# Sensor_Board_Layout.net
KiCad netlist of a schematic drawn in EAGLE
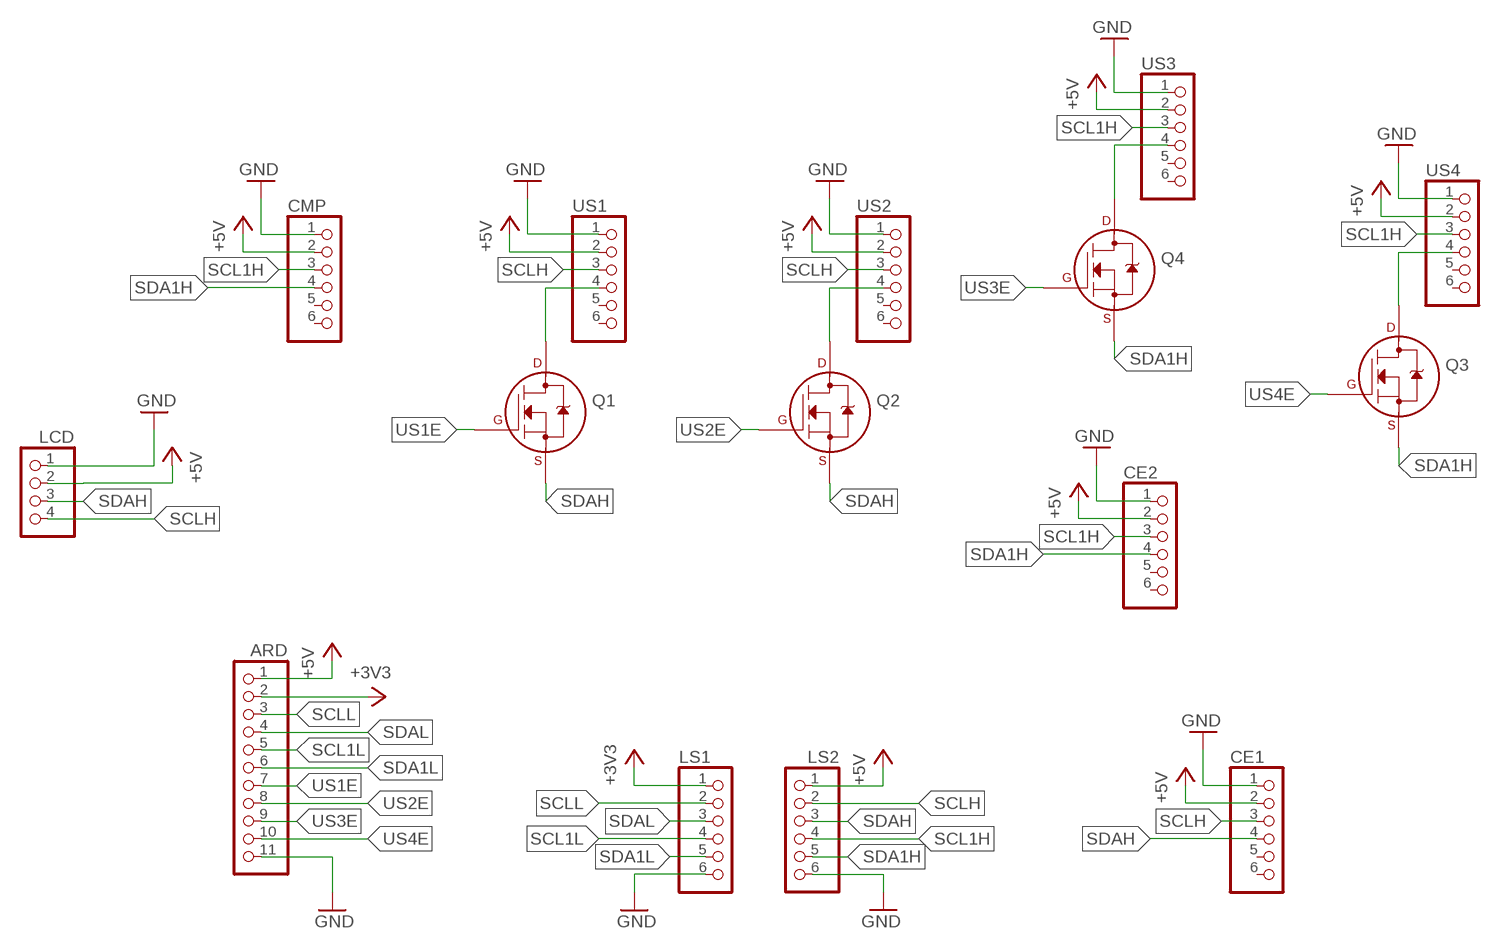
[diagram p0: schematic, sheet 1]

(export (version "E")
  (design (tool "Eeschema 10.0.6"))
  (components
    (comp (ref "ARD")
      (value "PINHD-1X11")
      (footprint "eagle-import:1X11")
      (libsource (lib "eagle-import") (part "PINHD-1X11"))
    )
    (comp (ref "CE1")
      (value "PINHD-1X6")
      (footprint "eagle-import:1X06")
      (libsource (lib "eagle-import") (part "PINHD-1X6"))
    )
    (comp (ref "CE2")
      (value "PINHD-1X6")
      (footprint "eagle-import:1X06")
      (libsource (lib "eagle-import") (part "PINHD-1X6"))
    )
    (comp (ref "CMP")
      (value "PINHD-1X6")
      (footprint "eagle-import:1X06")
      (libsource (lib "eagle-import") (part "PINHD-1X6"))
    )
    (comp (ref "LCD")
      (value "PINHD-1X4")
      (footprint "eagle-import:1X04")
      (libsource (lib "eagle-import") (part "PINHD-1X4"))
    )
    (comp (ref "LS1")
      (value "PINHD-1X6")
      (footprint "eagle-import:1X06")
      (libsource (lib "eagle-import") (part "PINHD-1X6"))
    )
    (comp (ref "LS2")
      (value "PINHD-1X6")
      (footprint "eagle-import:1X06")
      (libsource (lib "eagle-import") (part "PINHD-1X6"))
    )
    (comp (ref "Q1")
      (value "2N7000_TO92")
      (footprint "eagle-import:TO-92")
      (libsource (lib "eagle-import") (part "2N700_TO920"))
    )
    (comp (ref "Q2")
      (value "2N7000_TO92")
      (footprint "eagle-import:TO-92")
      (libsource (lib "eagle-import") (part "2N700_TO920"))
    )
    (comp (ref "Q3")
      (value "2N7000_TO92")
      (footprint "eagle-import:TO-92")
      (libsource (lib "eagle-import") (part "2N700_TO920"))
    )
    (comp (ref "Q4")
      (value "2N7000_TO92")
      (footprint "eagle-import:TO-92")
      (libsource (lib "eagle-import") (part "2N700_TO920"))
    )
    (comp (ref "US1")
      (value "PINHD-1X6")
      (footprint "eagle-import:1X06")
      (libsource (lib "eagle-import") (part "PINHD-1X6"))
    )
    (comp (ref "US2")
      (value "PINHD-1X6")
      (footprint "eagle-import:1X06")
      (libsource (lib "eagle-import") (part "PINHD-1X6"))
    )
    (comp (ref "US3")
      (value "PINHD-1X6")
      (footprint "eagle-import:1X06")
      (libsource (lib "eagle-import") (part "PINHD-1X6"))
    )
    (comp (ref "US4")
      (value "PINHD-1X6")
      (footprint "eagle-import:1X06")
      (libsource (lib "eagle-import") (part "PINHD-1X6"))
    )
  )
  (nets
    (net (code "1") (name "+3V3") (class "Default")
      (node (ref "ARD") (pin "2") (pinfunction "2_2") (pintype "passive"))
      (node (ref "LS1") (pin "1") (pinfunction "1_1") (pintype "passive"))
    )
    (net (code "2") (name "+5V") (class "Default")
      (node (ref "ARD") (pin "1") (pinfunction "1_1") (pintype "passive"))
      (node (ref "CE1") (pin "2") (pinfunction "2_2") (pintype "passive"))
      (node (ref "CE2") (pin "2") (pinfunction "2_2") (pintype "passive"))
      (node (ref "CMP") (pin "2") (pinfunction "2_2") (pintype "passive"))
      (node (ref "LCD") (pin "2") (pinfunction "2_2") (pintype "passive"))
      (node (ref "LS2") (pin "1") (pinfunction "1_1") (pintype "passive"))
      (node (ref "US1") (pin "2") (pinfunction "2_2") (pintype "passive"))
      (node (ref "US2") (pin "2") (pinfunction "2_2") (pintype "passive"))
      (node (ref "US3") (pin "2") (pinfunction "2_2") (pintype "passive"))
      (node (ref "US4") (pin "2") (pinfunction "2_2") (pintype "passive"))
    )
    (net (code "3") (name "GND") (class "Default")
      (node (ref "ARD") (pin "11") (pinfunction "11_11") (pintype "passive"))
      (node (ref "CE1") (pin "1") (pinfunction "1_1") (pintype "passive"))
      (node (ref "CE2") (pin "1") (pinfunction "1_1") (pintype "passive"))
      (node (ref "CMP") (pin "1") (pinfunction "1_1") (pintype "passive"))
      (node (ref "LCD") (pin "1") (pinfunction "1_1") (pintype "passive"))
      (node (ref "LS1") (pin "6") (pinfunction "6_6") (pintype "passive"))
      (node (ref "LS2") (pin "6") (pinfunction "6_6") (pintype "passive"))
      (node (ref "US1") (pin "1") (pinfunction "1_1") (pintype "passive"))
      (node (ref "US2") (pin "1") (pinfunction "1_1") (pintype "passive"))
      (node (ref "US3") (pin "1") (pinfunction "1_1") (pintype "passive"))
      (node (ref "US4") (pin "1") (pinfunction "1_1") (pintype "passive"))
    )
    (net (code "4") (name "Net-(Q1-D)") (class "Default")
      (node (ref "Q1") (pin "3") (pinfunction "D_3") (pintype "bidirectional"))
      (node (ref "US1") (pin "4") (pinfunction "4_4") (pintype "passive"))
    )
    (net (code "5") (name "Net-(Q2-D)") (class "Default")
      (node (ref "Q2") (pin "3") (pinfunction "D_3") (pintype "bidirectional"))
      (node (ref "US2") (pin "4") (pinfunction "4_4") (pintype "passive"))
    )
    (net (code "6") (name "Net-(Q3-D)") (class "Default")
      (node (ref "Q3") (pin "3") (pinfunction "D_3") (pintype "bidirectional"))
      (node (ref "US4") (pin "4") (pinfunction "4_4") (pintype "passive"))
    )
    (net (code "7") (name "Net-(Q4-D)") (class "Default")
      (node (ref "Q4") (pin "3") (pinfunction "D_3") (pintype "bidirectional"))
      (node (ref "US3") (pin "4") (pinfunction "4_4") (pintype "passive"))
    )
    (net (code "8") (name "SCL1H") (class "Default")
      (node (ref "CE2") (pin "3") (pinfunction "3_3") (pintype "passive"))
      (node (ref "CMP") (pin "3") (pinfunction "3_3") (pintype "passive"))
      (node (ref "LS2") (pin "4") (pinfunction "4_4") (pintype "passive"))
      (node (ref "US3") (pin "3") (pinfunction "3_3") (pintype "passive"))
      (node (ref "US4") (pin "3") (pinfunction "3_3") (pintype "passive"))
    )
    (net (code "9") (name "SCL1L") (class "Default")
      (node (ref "ARD") (pin "5") (pinfunction "5_5") (pintype "passive"))
      (node (ref "LS1") (pin "4") (pinfunction "4_4") (pintype "passive"))
    )
    (net (code "10") (name "SCLH") (class "Default")
      (node (ref "CE1") (pin "3") (pinfunction "3_3") (pintype "passive"))
      (node (ref "LCD") (pin "4") (pinfunction "4_4") (pintype "passive"))
      (node (ref "LS2") (pin "2") (pinfunction "2_2") (pintype "passive"))
      (node (ref "US1") (pin "3") (pinfunction "3_3") (pintype "passive"))
      (node (ref "US2") (pin "3") (pinfunction "3_3") (pintype "passive"))
    )
    (net (code "11") (name "SCLL") (class "Default")
      (node (ref "ARD") (pin "3") (pinfunction "3_3") (pintype "passive"))
      (node (ref "LS1") (pin "2") (pinfunction "2_2") (pintype "passive"))
    )
    (net (code "12") (name "SDA1H") (class "Default")
      (node (ref "CE2") (pin "4") (pinfunction "4_4") (pintype "passive"))
      (node (ref "CMP") (pin "4") (pinfunction "4_4") (pintype "passive"))
      (node (ref "LS2") (pin "5") (pinfunction "5_5") (pintype "passive"))
      (node (ref "Q3") (pin "1") (pinfunction "S_1") (pintype "bidirectional"))
    )
    (net (code "13") (name "SDA1L") (class "Default")
      (node (ref "ARD") (pin "6") (pinfunction "6_6") (pintype "passive"))
      (node (ref "LS1") (pin "5") (pinfunction "5_5") (pintype "passive"))
    )
    (net (code "14") (name "SDAH") (class "Default")
      (node (ref "CE1") (pin "4") (pinfunction "4_4") (pintype "passive"))
      (node (ref "LCD") (pin "3") (pinfunction "3_3") (pintype "passive"))
      (node (ref "LS2") (pin "3") (pinfunction "3_3") (pintype "passive"))
      (node (ref "Q1") (pin "1") (pinfunction "S_1") (pintype "bidirectional"))
      (node (ref "Q2") (pin "1") (pinfunction "S_1") (pintype "bidirectional"))
    )
    (net (code "15") (name "SDAL") (class "Default")
      (node (ref "ARD") (pin "4") (pinfunction "4_4") (pintype "passive"))
      (node (ref "LS1") (pin "3") (pinfunction "3_3") (pintype "passive"))
    )
    (net (code "16") (name "US1E") (class "Default")
      (node (ref "ARD") (pin "7") (pinfunction "7_7") (pintype "passive"))
      (node (ref "Q1") (pin "2") (pinfunction "G_2") (pintype "tri_state"))
    )
    (net (code "17") (name "US2E") (class "Default")
      (node (ref "ARD") (pin "8") (pinfunction "8_8") (pintype "passive"))
      (node (ref "Q2") (pin "2") (pinfunction "G_2") (pintype "tri_state"))
    )
    (net (code "18") (name "US3E") (class "Default")
      (node (ref "ARD") (pin "9") (pinfunction "9_9") (pintype "passive"))
      (node (ref "Q4") (pin "2") (pinfunction "G_2") (pintype "tri_state"))
    )
    (net (code "19") (name "US4E") (class "Default")
      (node (ref "ARD") (pin "10") (pinfunction "10_10") (pintype "passive"))
      (node (ref "Q3") (pin "2") (pinfunction "G_2") (pintype "tri_state"))
    )
    (net (code "20") (name "unconnected-(CE1-Pad5)") (class "Default")
      (node (ref "CE1") (pin "5") (pinfunction "5_5") (pintype "passive"))
    )
    (net (code "21") (name "unconnected-(CE1-Pad6)") (class "Default")
      (node (ref "CE1") (pin "6") (pinfunction "6_6") (pintype "passive"))
    )
    (net (code "22") (name "unconnected-(CE2-Pad5)") (class "Default")
      (node (ref "CE2") (pin "5") (pinfunction "5_5") (pintype "passive"))
    )
    (net (code "23") (name "unconnected-(CE2-Pad6)") (class "Default")
      (node (ref "CE2") (pin "6") (pinfunction "6_6") (pintype "passive"))
    )
    (net (code "24") (name "unconnected-(CMP-Pad5)") (class "Default")
      (node (ref "CMP") (pin "5") (pinfunction "5_5") (pintype "passive"))
    )
    (net (code "25") (name "unconnected-(CMP-Pad6)") (class "Default")
      (node (ref "CMP") (pin "6") (pinfunction "6_6") (pintype "passive"))
    )
    (net (code "26") (name "unconnected-(Q4-S-Pad1)") (class "Default")
      (node (ref "Q4") (pin "1") (pinfunction "S_1") (pintype "bidirectional"))
    )
    (net (code "27") (name "unconnected-(US1-Pad5)") (class "Default")
      (node (ref "US1") (pin "5") (pinfunction "5_5") (pintype "passive"))
    )
    (net (code "28") (name "unconnected-(US1-Pad6)") (class "Default")
      (node (ref "US1") (pin "6") (pinfunction "6_6") (pintype "passive"))
    )
    (net (code "29") (name "unconnected-(US2-Pad5)") (class "Default")
      (node (ref "US2") (pin "5") (pinfunction "5_5") (pintype "passive"))
    )
    (net (code "30") (name "unconnected-(US2-Pad6)") (class "Default")
      (node (ref "US2") (pin "6") (pinfunction "6_6") (pintype "passive"))
    )
    (net (code "31") (name "unconnected-(US3-Pad5)") (class "Default")
      (node (ref "US3") (pin "5") (pinfunction "5_5") (pintype "passive"))
    )
    (net (code "32") (name "unconnected-(US3-Pad6)") (class "Default")
      (node (ref "US3") (pin "6") (pinfunction "6_6") (pintype "passive"))
    )
    (net (code "33") (name "unconnected-(US4-Pad5)") (class "Default")
      (node (ref "US4") (pin "5") (pinfunction "5_5") (pintype "passive"))
    )
    (net (code "34") (name "unconnected-(US4-Pad6)") (class "Default")
      (node (ref "US4") (pin "6") (pinfunction "6_6") (pintype "passive"))
    )
  )
)
